# Sensor_BoardSchDoc.net
KiCad netlist of a schematic drawn in Altium Designer
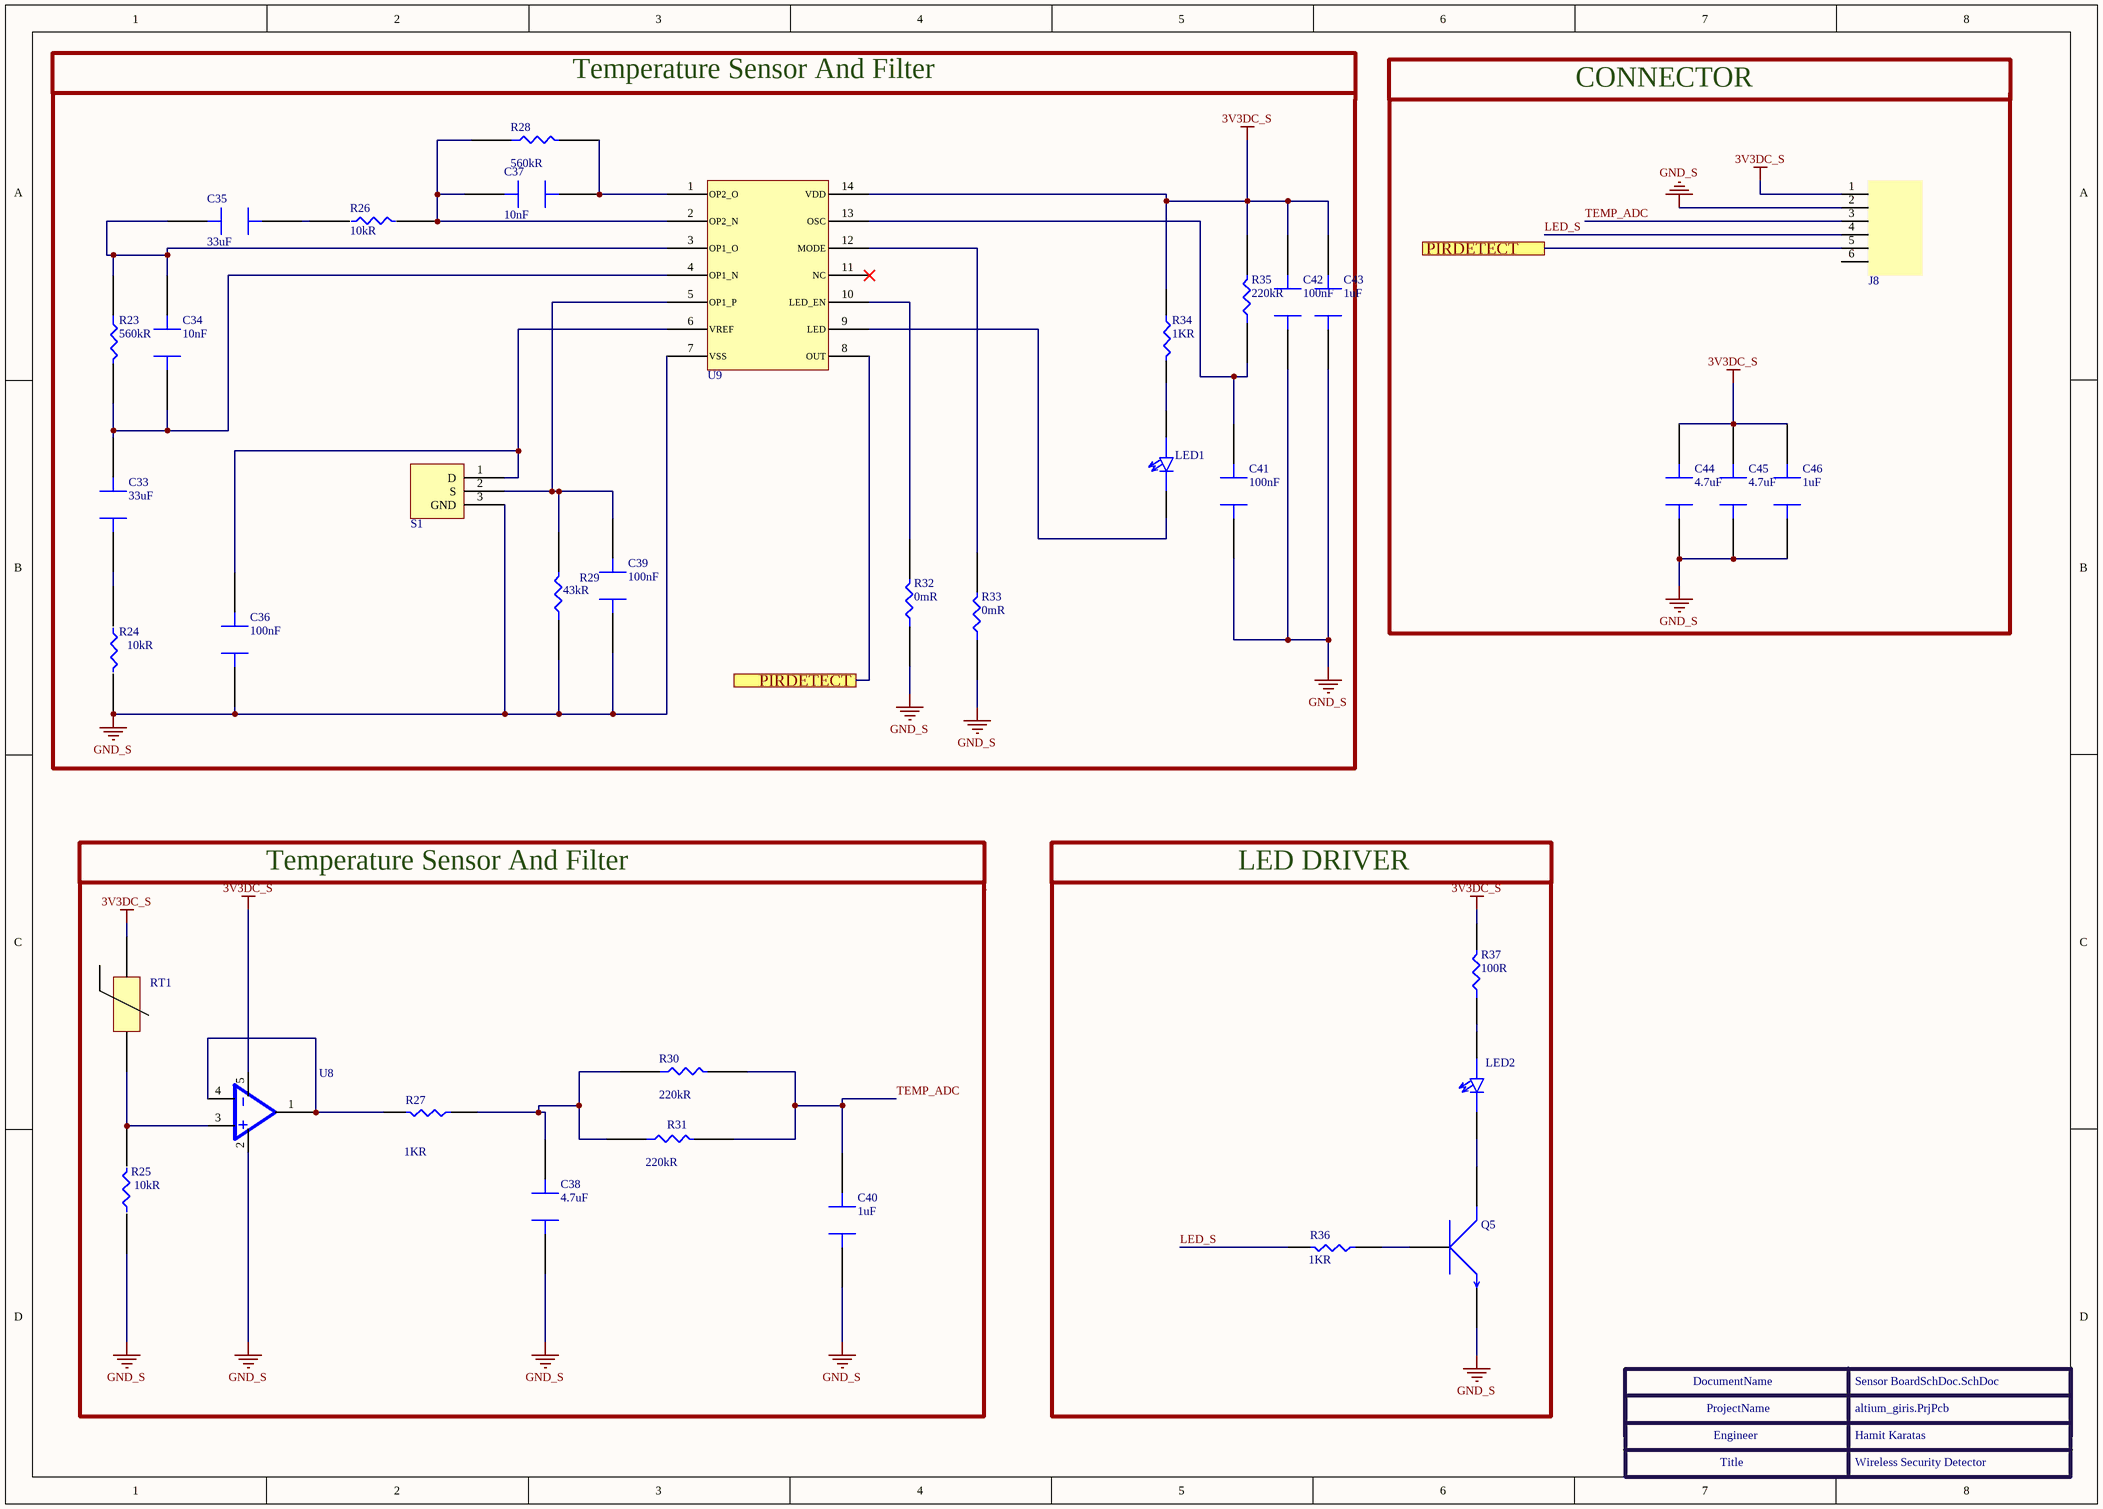
[diagram p0: Sensor BoardSchDoc.SchDoc]

(export (version "E")
  (design (tool "Eeschema 10.0.6"))
  (components
    (comp (ref "C33")
      (value "C3216X5R1E336M160AC")
      (footprint "CAP_1206")
      (description "Cap Ceramic 33uF 25V X5R 20% SMD 1206 85C T/R")
      (fields
        (field (name "MANUFACTURER") "TDK")
        (field (name "TOLERANCE") "20%")
        (field (name "CAPACITANCE") "33uF")
        (field (name "DESIGNED BY") "Hamit")
      )
      (libsource (lib "giris_intlib") (part "CAP CER 33uF 1206"))
    )
    (comp (ref "C34")
      (value "C0805C103K1RAC")
      (footprint "cap_0805")
      (description "Cap Ceramic 0.01uF 100V X7R 10% Pad SMD 0805 125C Bulk")
      (fields
        (field (name "MANUFACTURER") "KEMET")
        (field (name "TOLERANCE") "10%")
        (field (name "CAPACITANCE") "10nF")
        (field (name "DESIGNED BY") "Hamit")
      )
      (libsource (lib "giris_intlib") (part "CAP CER 10nF"))
    )
    (comp (ref "C35")
      (value "C3216X5R1E336M160AC")
      (footprint "CAP_1206")
      (description "Cap Ceramic 33uF 25V X5R 20% SMD 1206 85C T/R")
      (fields
        (field (name "MANUFACTURER") "TDK")
        (field (name "TOLERANCE") "20%")
        (field (name "CAPACITANCE") "33uF")
        (field (name "DESIGNED BY") "Hamit")
      )
      (libsource (lib "giris_intlib") (part "CAP CER 33uF 1206"))
    )
    (comp (ref "C36")
      (value "CL21B104KBCNNNC")
      (footprint "cap_0805")
      (fields
        (field (name "MANUFACTURER") "Samsung")
        (field (name "TOLERANCE") "10%")
        (field (name "VOLTAGE") "50V")
        (field (name "CAPACITANCE") "100nF")
        (field (name "DESIGNED BY") "Hamit")
      )
      (libsource (lib "giris_intlib") (part "CAP cer 100nF 0805"))
    )
    (comp (ref "C37")
      (value "C0805C103K1RAC")
      (footprint "cap_0805")
      (description "Cap Ceramic 0.01uF 100V X7R 10% Pad SMD 0805 125C Bulk")
      (fields
        (field (name "MANUFACTURER") "KEMET")
        (field (name "TOLERANCE") "10%")
        (field (name "CAPACITANCE") "10nF")
        (field (name "DESIGNED BY") "Hamit")
      )
      (libsource (lib "giris_intlib") (part "CAP CER 10nF"))
    )
    (comp (ref "C38")
      (value "CL21A475KAQNNNE")
      (footprint "cap_0805")
      (fields
        (field (name "MANUFACTURER") "Samsung")
        (field (name "TOLERANCE") "10%")
        (field (name "CAPACITANCE") "4.7uF")
        (field (name "DESIGNED BY") "Hamit")
      )
      (libsource (lib "giris_intlib") (part "CAP CER 4.7 uF"))
    )
    (comp (ref "C39")
      (value "CL21B104KBCNNNC")
      (footprint "cap_0805")
      (fields
        (field (name "MANUFACTURER") "Samsung")
        (field (name "TOLERANCE") "10%")
        (field (name "VOLTAGE") "50V")
        (field (name "CAPACITANCE") "100nF")
        (field (name "DESIGNED BY") "Hamit")
      )
      (libsource (lib "giris_intlib") (part "CAP cer 100nF 0805"))
    )
    (comp (ref "C40")
      (value "CAP CER 1uF 0805")
      (footprint "cap_0805")
      (description "0805 0.1 uF ±10 % Tolerance 50 V X7R Multilayer Ceramic Capacitors")
      (fields
        (field (name "MANUFACTURER") "Samsung")
        (field (name "MANUFACTURER PART NUMBER") "CL21B104KBFNNNE")
        (field (name "CAPACITANCE") "1uF")
        (field (name "DESIGNED BY") "Hamit")
      )
      (libsource (lib "giris_intlib") (part "CAP CER 1uF 0805"))
    )
    (comp (ref "C41")
      (value "CL21B104KBCNNNC")
      (footprint "cap_0805")
      (fields
        (field (name "MANUFACTURER") "Samsung")
        (field (name "TOLERANCE") "10%")
        (field (name "VOLTAGE") "50V")
        (field (name "CAPACITANCE") "100nF")
        (field (name "DESIGNED BY") "Hamit")
      )
      (libsource (lib "giris_intlib") (part "CAP cer 100nF 0805"))
    )
    (comp (ref "C42")
      (value "CAP CER 100nF 0603")
      (footprint "CAP_0603")
      (fields
        (field (name "MANUFACTURER") "KEMET")
        (field (name "MANUFACTURER PART NUMBER") "C0603C104K5RACTU")
        (field (name "TOLERANCE") "10%")
        (field (name "CAPACITANCE") "100nF")
        (field (name "DESIGNED BY") "Hamit")
      )
      (libsource (lib "giris_intlib") (part "CAP CER 100nF 0603"))
    )
    (comp (ref "C43")
      (value "CAP CER 1uF 0805")
      (footprint "cap_0805")
      (description "0805 0.1 uF ±10 % Tolerance 50 V X7R Multilayer Ceramic Capacitors")
      (fields
        (field (name "MANUFACTURER") "Samsung")
        (field (name "MANUFACTURER PART NUMBER") "CL21B104KBFNNNE")
        (field (name "CAPACITANCE") "1uF")
        (field (name "DESIGNED BY") "Hamit")
      )
      (libsource (lib "giris_intlib") (part "CAP CER 1uF 0805"))
    )
    (comp (ref "C44")
      (value "CL21A475KAQNNNE")
      (footprint "cap_0805")
      (fields
        (field (name "MANUFACTURER") "Samsung")
        (field (name "TOLERANCE") "10%")
        (field (name "CAPACITANCE") "4.7uF")
        (field (name "DESIGNED BY") "Hamit")
      )
      (libsource (lib "giris_intlib") (part "CAP CER 4.7 uF"))
    )
    (comp (ref "C45")
      (value "CL21A475KAQNNNE")
      (footprint "cap_0805")
      (fields
        (field (name "MANUFACTURER") "Samsung")
        (field (name "TOLERANCE") "10%")
        (field (name "CAPACITANCE") "4.7uF")
        (field (name "DESIGNED BY") "Hamit")
      )
      (libsource (lib "giris_intlib") (part "CAP CER 4.7 uF"))
    )
    (comp (ref "C46")
      (value "CAP CER 1uF 0805")
      (footprint "cap_0805")
      (description "0805 0.1 uF ±10 % Tolerance 50 V X7R Multilayer Ceramic Capacitors")
      (fields
        (field (name "MANUFACTURER") "Samsung")
        (field (name "MANUFACTURER PART NUMBER") "CL21B104KBFNNNE")
        (field (name "CAPACITANCE") "1uF")
        (field (name "DESIGNED BY") "Hamit")
      )
      (libsource (lib "giris_intlib") (part "CAP CER 1uF 0805"))
    )
    (comp (ref "J8")
      (value "64800611622_")
      (footprint "1.5mm 6pin connector")
      (description "6 PIN connector")
      (fields
        (field (name "MANUFACTURER") "Wurth Electronics")
        (field (name "MANUFACTURER PART NUMBER") "64800611622")
        (field (name "DESIGNED BY") "Hamit")
      )
      (libsource (lib "giris_intlib") (part "1.5mm_connector_6pin"))
    )
    (comp (ref "LED1")
      (value "LTST-C171GKT")
      (footprint "LED GREEN 0805")
      (description "Green 0805 130 º Min 5 mcd Typical 12 mcd Water Clear Lens SMT LED")
      (fields (field (name "MANUFACTURER") "Vishay Lite-On") (field (name "DESIGNED BY") "Hamit"))
      (libsource (lib "giris_intlib") (part "LED GREEN 0805"))
    )
    (comp (ref "LED2")
      (value "LH R974-LP-1")
      (footprint "LED RED 0805")
      (description "Single Color LED, Hyper Red, Colorless Diffused, 1.3mm")
      (fields (field (name "MANUFACTURER") "Osram Opto") (field (name "DESIGNED BY") "Hamit"))
      (libsource (lib "giris_intlib") (part "LED RED 0805"))
    )
    (comp (ref "Q5")
      (value "MMBT3904-7-F")
      (footprint "SSM3K357R,LF")
      (description "Transistor General Purpose BJT NPN 40 Volt 0.2A Automotive 3-Pin SOT-23")
      (fields (field (name "MANUFACTURER") "Diodes Zetex") (field (name "DESIGNED BY") "Hamit"))
      (libsource (lib "giris_intlib") (part "MMBT3904-7-F"))
    )
    (comp (ref "R23")
      (value "RC0603JR-07560KL")
      (footprint "RES_0603")
      (description "RES SMD 560K OHM 5% 1/10W 0603")
      (fields
        (field (name "MANUFACTURER") "Yageo")
        (field (name "TOLERANCE") "5%")
        (field (name "RESISTANCE") "560kR")
        (field (name "DESIGNED BY") "Hamit")
      )
      (libsource (lib "giris_intlib") (part "RES 560K OHM %5"))
    )
    (comp (ref "R24")
      (value "RES 10K OHM 0603")
      (footprint "RES_0603")
      (description "Res General Purpose Thick Film 0603 10K Ohm 1% 1/10W ±100ppm/°C Molded SMD Paper T/R")
      (fields
        (field (name "MANUFACTURER") "Yageo")
        (field (name "MANUFACTURER PART NUMBER") "RC0603FR-0710KL")
        (field (name "RESISTANCE") "10kR")
        (field (name "DESIGNED BY") "Hamit")
      )
      (libsource (lib "giris_intlib") (part "RES 10K OHM 0603"))
    )
    (comp (ref "R25")
      (value "RES 10K OHM 0603")
      (footprint "RES_0603")
      (description "Res General Purpose Thick Film 0603 10K Ohm 1% 1/10W ±100ppm/°C Molded SMD Paper T/R")
      (fields
        (field (name "MANUFACTURER") "Yageo")
        (field (name "MANUFACTURER PART NUMBER") "RC0603FR-0710KL")
        (field (name "RESISTANCE") "10kR")
        (field (name "DESIGNED BY") "Hamit")
      )
      (libsource (lib "giris_intlib") (part "RES 10K OHM 0603"))
    )
    (comp (ref "R26")
      (value "RES 10K OHM 0603")
      (footprint "RES_0603")
      (description "Res General Purpose Thick Film 0603 10K Ohm 1% 1/10W ±100ppm/°C Molded SMD Paper T/R")
      (fields
        (field (name "MANUFACTURER") "Yageo")
        (field (name "MANUFACTURER PART NUMBER") "RC0603FR-0710KL")
        (field (name "RESISTANCE") "10kR")
        (field (name "DESIGNED BY") "Hamit")
      )
      (libsource (lib "giris_intlib") (part "RES 10K OHM 0603"))
    )
    (comp (ref "R27")
      (value "RC0603FR-0710KL")
      (footprint "RES_0603")
      (description "RES 1K %1 OHM 0603 SMD")
      (fields
        (field (name "MANUFACTURER") "Yageo")
        (field (name "MANUFACTURER PART NUMBER") "RC0603JR-071KL")
        (field (name "RESISTANCE") "1KR")
        (field (name "DESIGNED BY") "Hamit")
      )
      (libsource (lib "giris_intlib") (part "RES 1K OHM 0603"))
    )
    (comp (ref "R28")
      (value "RC0603JR-07560KL")
      (footprint "RES_0603")
      (description "RES SMD 560K OHM 5% 1/10W 0603")
      (fields
        (field (name "MANUFACTURER") "Yageo")
        (field (name "TOLERANCE") "5%")
        (field (name "RESISTANCE") "560kR")
        (field (name "DESIGNED BY") "Hamit")
      )
      (libsource (lib "giris_intlib") (part "RES 560K OHM %5"))
    )
    (comp (ref "R29")
      (value "RC0603JR-0743KL")
      (footprint "RES_0603")
      (fields
        (field (name "MANUFACTURER") "Yageo")
        (field (name "TOLERANCE") "5%")
        (field (name "RESISTANCE") "43kR")
        (field (name "DESIGNED BY") "Hamit")
      )
      (libsource (lib "giris_intlib") (part "RES 43K OHM %5"))
    )
    (comp (ref "R30")
      (value "RC0603JR-07220KL")
      (footprint "RES_0603")
      (fields
        (field (name "MANUFACTURER") "Yageo")
        (field (name "TOLERANCE") "5%")
        (field (name "RESISTANCE") "220kR")
        (field (name "DESIGNED BY") "Hamit")
      )
      (libsource (lib "giris_intlib") (part "RES 220K OHM %5"))
    )
    (comp (ref "R31")
      (value "RC0603JR-07220KL")
      (footprint "RES_0603")
      (fields
        (field (name "MANUFACTURER") "Yageo")
        (field (name "TOLERANCE") "5%")
        (field (name "RESISTANCE") "220kR")
        (field (name "DESIGNED BY") "Hamit")
      )
      (libsource (lib "giris_intlib") (part "RES 220K OHM %5"))
    )
    (comp (ref "R32")
      (value "RC0603JR-070RL")
      (footprint "RES_0603")
      (description "RES SMD 0 OHM JUMPER 1/10W 0603")
      (fields
        (field (name "MANUFACTURER") "Yageo")
        (field (name "TOLERANCE") "1%")
        (field (name "RESISTANCE") "0mR")
        (field (name "DESIGNED BY") "Hamit")
      )
      (libsource (lib "giris_intlib") (part "Res 0 ohm 0603"))
    )
    (comp (ref "R33")
      (value "RC0603JR-070RL")
      (footprint "RES_0603")
      (description "RES SMD 0 OHM JUMPER 1/10W 0603")
      (fields
        (field (name "MANUFACTURER") "Yageo")
        (field (name "TOLERANCE") "1%")
        (field (name "RESISTANCE") "0mR")
        (field (name "DESIGNED BY") "Hamit")
      )
      (libsource (lib "giris_intlib") (part "Res 0 ohm 0603"))
    )
    (comp (ref "R34")
      (value "RC0603FR-0710KL")
      (footprint "RES_0603")
      (description "RES 1K %1 OHM 0603 SMD")
      (fields
        (field (name "MANUFACTURER") "Yageo")
        (field (name "MANUFACTURER PART NUMBER") "RC0603JR-071KL")
        (field (name "RESISTANCE") "1KR")
        (field (name "DESIGNED BY") "Hamit")
      )
      (libsource (lib "giris_intlib") (part "RES 1K OHM 0603"))
    )
    (comp (ref "R35")
      (value "RC0603JR-07220KL")
      (footprint "RES_0603")
      (fields
        (field (name "MANUFACTURER") "Yageo")
        (field (name "TOLERANCE") "5%")
        (field (name "RESISTANCE") "220kR")
        (field (name "DESIGNED BY") "Hamit")
      )
      (libsource (lib "giris_intlib") (part "RES 220K OHM %5"))
    )
    (comp (ref "R36")
      (value "RC0603FR-0710KL")
      (footprint "RES_0603")
      (description "RES 1K %1 OHM 0603 SMD")
      (fields
        (field (name "MANUFACTURER") "Yageo")
        (field (name "MANUFACTURER PART NUMBER") "RC0603JR-071KL")
        (field (name "RESISTANCE") "1KR")
        (field (name "DESIGNED BY") "Hamit")
      )
      (libsource (lib "giris_intlib") (part "RES 1K OHM 0603"))
    )
    (comp (ref "R37")
      (value "RC0603FR-7W100RL")
      (footprint "RES_0603")
      (description "RESISTOR, 0603, 100R, 1%")
      (fields
        (field (name "MANUFACTURER") "Yageo")
        (field (name "TOLERANCE") "1%")
        (field (name "RESISTANCE") "100R")
      )
      (libsource (lib "giris_intlib") (part "RES 100 OHm"))
    )
    (comp (ref "RT1")
      (value "TFPT1206L1002FM")
      (footprint "res_1206")
      (description "Thermistor PTC 10K Ohm 1% 2-Pin 1206 Surface Mount Solder Pad T/R Automotive")
      (fields
        (field (name "MANUFACTURER") "Vishay Dale")
        (field (name "TOLERANCE") "1%")
        (field (name "DESIGNED BY") "Hamit")
      )
      (libsource (lib "giris_intlib") (part "TFPT1206L1002FM"))
    )
    (comp (ref "S1")
      (value "LHI 878/3902")
      (footprint "LHI 878/3902 - duplicate")
      (description "PIR")
      (fields (field (name "DESIGNED BY") "Hamit"))
      (libsource (lib "giris_intlib") (part "LHI 878/3902"))
    )
    (comp (ref "U8")
      (value "OPA314AIDBVR")
      (footprint "SOT23-5")
      (description "Op Amp SOT-23-5 Amplifiers - Op Amps, Buffer, Instrumentation")
      (fields (field (name "MANUFACTURER") "Texas Instruments") (field (name "DESIGNED BY") "Hamit"))
      (libsource (lib "giris_intlib") (part "OPA314"))
    )
    (comp (ref "U9")
      (value "NCS36000DRG")
      (footprint "SOIC14")
      (description "PIR CONTROLLERLow Noise Amplifiers and LDO Regulator 14-Pin SOIC N T/R")
      (fields (field (name "MANUFACTURER") "ON Semiconductor") (field (name "DESIGNED BY") "Hamit"))
      (libsource (lib "giris_intlib") (part "NCS36000"))
    )
  )
  (nets
    (net (code "1") (name "/LED_S") (class "Default")
      (node (ref "J8") (pin "4") (pintype "passive"))
      (node (ref "R36") (pin "1") (pinfunction "1_1") (pintype "passive"))
    )
    (net (code "2") (name "/PIRDETECT") (class "Default")
      (node (ref "J8") (pin "5") (pintype "passive"))
      (node (ref "U9") (pin "8") (pinfunction "OUT_8") (pintype "passive"))
    )
    (net (code "3") (name "/TEMP_ADC") (class "Default")
      (node (ref "C40") (pin "2") (pinfunction "2_2") (pintype "passive"))
      (node (ref "J8") (pin "3") (pintype "passive"))
      (node (ref "R30") (pin "2") (pinfunction "2_2") (pintype "passive"))
      (node (ref "R31") (pin "2") (pinfunction "2_2") (pintype "passive"))
    )
    (net (code "4") (name "3V3DC_S") (class "Default")
      (node (ref "C42") (pin "2") (pinfunction "2_2") (pintype "passive"))
      (node (ref "C43") (pin "2") (pinfunction "2_2") (pintype "passive"))
      (node (ref "C44") (pin "2") (pinfunction "2_2") (pintype "passive"))
      (node (ref "C45") (pin "2") (pinfunction "2_2") (pintype "passive"))
      (node (ref "C46") (pin "2") (pinfunction "2_2") (pintype "passive"))
      (node (ref "J8") (pin "1") (pintype "passive"))
      (node (ref "R34") (pin "2") (pinfunction "2_2") (pintype "passive"))
      (node (ref "R35") (pin "2") (pinfunction "2_2") (pintype "passive"))
      (node (ref "R37") (pin "2") (pinfunction "2_2") (pintype "passive"))
      (node (ref "RT1") (pin "0") (pinfunction "0_0") (pintype "passive"))
      (node (ref "U8") (pin "5") (pinfunction "5_5") (pintype "passive"))
      (node (ref "U9") (pin "14") (pinfunction "VDD_14") (pintype "passive"))
    )
    (net (code "5") (name "GND_S") (class "Default")
      (node (ref "C36") (pin "1") (pinfunction "1_1") (pintype "passive"))
      (node (ref "C38") (pin "1") (pinfunction "1_1") (pintype "passive"))
      (node (ref "C39") (pin "1") (pinfunction "1_1") (pintype "passive"))
      (node (ref "C40") (pin "1") (pinfunction "1_1") (pintype "passive"))
      (node (ref "C41") (pin "1") (pinfunction "1_1") (pintype "passive"))
      (node (ref "C42") (pin "1") (pinfunction "1_1") (pintype "passive"))
      (node (ref "C43") (pin "1") (pinfunction "1_1") (pintype "passive"))
      (node (ref "C44") (pin "1") (pinfunction "1_1") (pintype "passive"))
      (node (ref "C45") (pin "1") (pinfunction "1_1") (pintype "passive"))
      (node (ref "C46") (pin "1") (pinfunction "1_1") (pintype "passive"))
      (node (ref "J8") (pin "2") (pintype "passive"))
      (node (ref "Q5") (pin "2") (pinfunction "E_2") (pintype "passive"))
      (node (ref "R24") (pin "2") (pinfunction "2_2") (pintype "passive"))
      (node (ref "R25") (pin "1") (pinfunction "1_1") (pintype "passive"))
      (node (ref "R29") (pin "1") (pinfunction "1_1") (pintype "passive"))
      (node (ref "R32") (pin "1") (pinfunction "1_1") (pintype "passive"))
      (node (ref "R33") (pin "1") (pinfunction "1_1") (pintype "passive"))
      (node (ref "S1") (pin "3") (pinfunction "GND_3") (pintype "passive"))
      (node (ref "U8") (pin "2") (pinfunction "2_2") (pintype "passive"))
      (node (ref "U9") (pin "7") (pinfunction "VSS_7") (pintype "passive"))
    )
    (net (code "6") (name "Net-(C33-Pad2)") (class "Default")
      (node (ref "C33") (pin "2") (pinfunction "2_2") (pintype "passive"))
      (node (ref "R24") (pin "1") (pinfunction "1_1") (pintype "passive"))
    )
    (net (code "7") (name "Net-(C35-Pad2)") (class "Default")
      (node (ref "C35") (pin "2") (pinfunction "2_2") (pintype "passive"))
      (node (ref "R26") (pin "1") (pinfunction "1_1") (pintype "passive"))
    )
    (net (code "8") (name "Net-(C38-Pad2)") (class "Default")
      (node (ref "C38") (pin "2") (pinfunction "2_2") (pintype "passive"))
      (node (ref "R27") (pin "2") (pinfunction "2_2") (pintype "passive"))
      (node (ref "R30") (pin "1") (pinfunction "1_1") (pintype "passive"))
      (node (ref "R31") (pin "1") (pinfunction "1_1") (pintype "passive"))
    )
    (net (code "9") (name "Net-(LED1-PadA)") (class "Default")
      (node (ref "LED1") (pin "A") (pinfunction "A_A") (pintype "passive"))
      (node (ref "R34") (pin "1") (pinfunction "1_1") (pintype "passive"))
    )
    (net (code "10") (name "Net-(LED2-PadA)") (class "Default")
      (node (ref "LED2") (pin "A") (pinfunction "A_A") (pintype "passive"))
      (node (ref "R37") (pin "1") (pinfunction "1_1") (pintype "passive"))
    )
    (net (code "11") (name "Net-(Q5-B)") (class "Default")
      (node (ref "Q5") (pin "1") (pinfunction "B_1") (pintype "passive"))
      (node (ref "R36") (pin "2") (pinfunction "2_2") (pintype "passive"))
    )
    (net (code "12") (name "Net-(Q5-C)") (class "Default")
      (node (ref "LED2") (pin "C") (pinfunction "C_C") (pintype "passive"))
      (node (ref "Q5") (pin "3") (pinfunction "C_3") (pintype "passive"))
    )
    (net (code "13") (name "Net-(R25-Pad2)") (class "Default")
      (node (ref "R25") (pin "2") (pinfunction "2_2") (pintype "passive"))
      (node (ref "RT1") (pin "1") (pinfunction "1_1") (pintype "passive"))
      (node (ref "U8") (pin "3") (pinfunction "3_3") (pintype "passive"))
    )
    (net (code "14") (name "Net-(R27-Pad1)") (class "Default")
      (node (ref "R27") (pin "1") (pinfunction "1_1") (pintype "passive"))
      (node (ref "U8") (pin "1") (pinfunction "1_1") (pintype "passive"))
      (node (ref "U8") (pin "4") (pinfunction "4_4") (pintype "passive"))
    )
    (net (code "15") (name "Net-(S1-D)") (class "Default")
      (node (ref "C36") (pin "2") (pinfunction "2_2") (pintype "passive"))
      (node (ref "S1") (pin "1") (pinfunction "D_1") (pintype "passive"))
      (node (ref "U9") (pin "6") (pinfunction "VREF_6") (pintype "passive"))
    )
    (net (code "16") (name "Net-(S1-S)") (class "Default")
      (node (ref "C39") (pin "2") (pinfunction "2_2") (pintype "passive"))
      (node (ref "R29") (pin "2") (pinfunction "2_2") (pintype "passive"))
      (node (ref "S1") (pin "2") (pinfunction "S_2") (pintype "passive"))
      (node (ref "U9") (pin "5") (pinfunction "OP1_P_5") (pintype "passive"))
    )
    (net (code "17") (name "Net-(U9-LED)") (class "Default")
      (node (ref "LED1") (pin "C") (pinfunction "C_C") (pintype "passive"))
      (node (ref "U9") (pin "9") (pinfunction "LED_9") (pintype "passive"))
    )
    (net (code "18") (name "Net-(U9-LED_EN)") (class "Default")
      (node (ref "R32") (pin "2") (pinfunction "2_2") (pintype "passive"))
      (node (ref "U9") (pin "10") (pinfunction "LED_EN_10") (pintype "passive"))
    )
    (net (code "19") (name "Net-(U9-MODE)") (class "Default")
      (node (ref "R33") (pin "2") (pinfunction "2_2") (pintype "passive"))
      (node (ref "U9") (pin "12") (pinfunction "MODE_12") (pintype "passive"))
    )
    (net (code "20") (name "Net-(U9-OP1_N)") (class "Default")
      (node (ref "C33") (pin "1") (pinfunction "1_1") (pintype "passive"))
      (node (ref "C34") (pin "2") (pinfunction "2_2") (pintype "passive"))
      (node (ref "R23") (pin "2") (pinfunction "2_2") (pintype "passive"))
      (node (ref "U9") (pin "4") (pinfunction "OP1_N_4") (pintype "passive"))
    )
    (net (code "21") (name "Net-(U9-OP1_O)") (class "Default")
      (node (ref "C34") (pin "1") (pinfunction "1_1") (pintype "passive"))
      (node (ref "C35") (pin "1") (pinfunction "1_1") (pintype "passive"))
      (node (ref "R23") (pin "1") (pinfunction "1_1") (pintype "passive"))
      (node (ref "U9") (pin "3") (pinfunction "OP1_O_3") (pintype "passive"))
    )
    (net (code "22") (name "Net-(U9-OP2_N)") (class "Default")
      (node (ref "C37") (pin "1") (pinfunction "1_1") (pintype "passive"))
      (node (ref "R26") (pin "2") (pinfunction "2_2") (pintype "passive"))
      (node (ref "R28") (pin "1") (pinfunction "1_1") (pintype "passive"))
      (node (ref "U9") (pin "2") (pinfunction "OP2_N_2") (pintype "passive"))
    )
    (net (code "23") (name "Net-(U9-OP2_O)") (class "Default")
      (node (ref "C37") (pin "2") (pinfunction "2_2") (pintype "passive"))
      (node (ref "R28") (pin "2") (pinfunction "2_2") (pintype "passive"))
      (node (ref "U9") (pin "1") (pinfunction "OP2_O_1") (pintype "passive"))
    )
    (net (code "24") (name "Net-(U9-OSC)") (class "Default")
      (node (ref "C41") (pin "2") (pinfunction "2_2") (pintype "passive"))
      (node (ref "R35") (pin "1") (pinfunction "1_1") (pintype "passive"))
      (node (ref "U9") (pin "13") (pinfunction "OSC_13") (pintype "passive"))
    )
    (net (code "25") (name "unconnected-(J8-Pad6)") (class "Default")
      (node (ref "J8") (pin "6") (pinfunction "6_6") (pintype "passive"))
    )
    (net (code "26") (name "unconnected-(U9-NC-Pad11)") (class "Default")
      (node (ref "U9") (pin "11") (pinfunction "NC_11") (pintype "passive+no_connect"))
    )
  )
)
